# RK3566_DDR4.net
KiCad netlist of a schematic drawn in Altium Designer
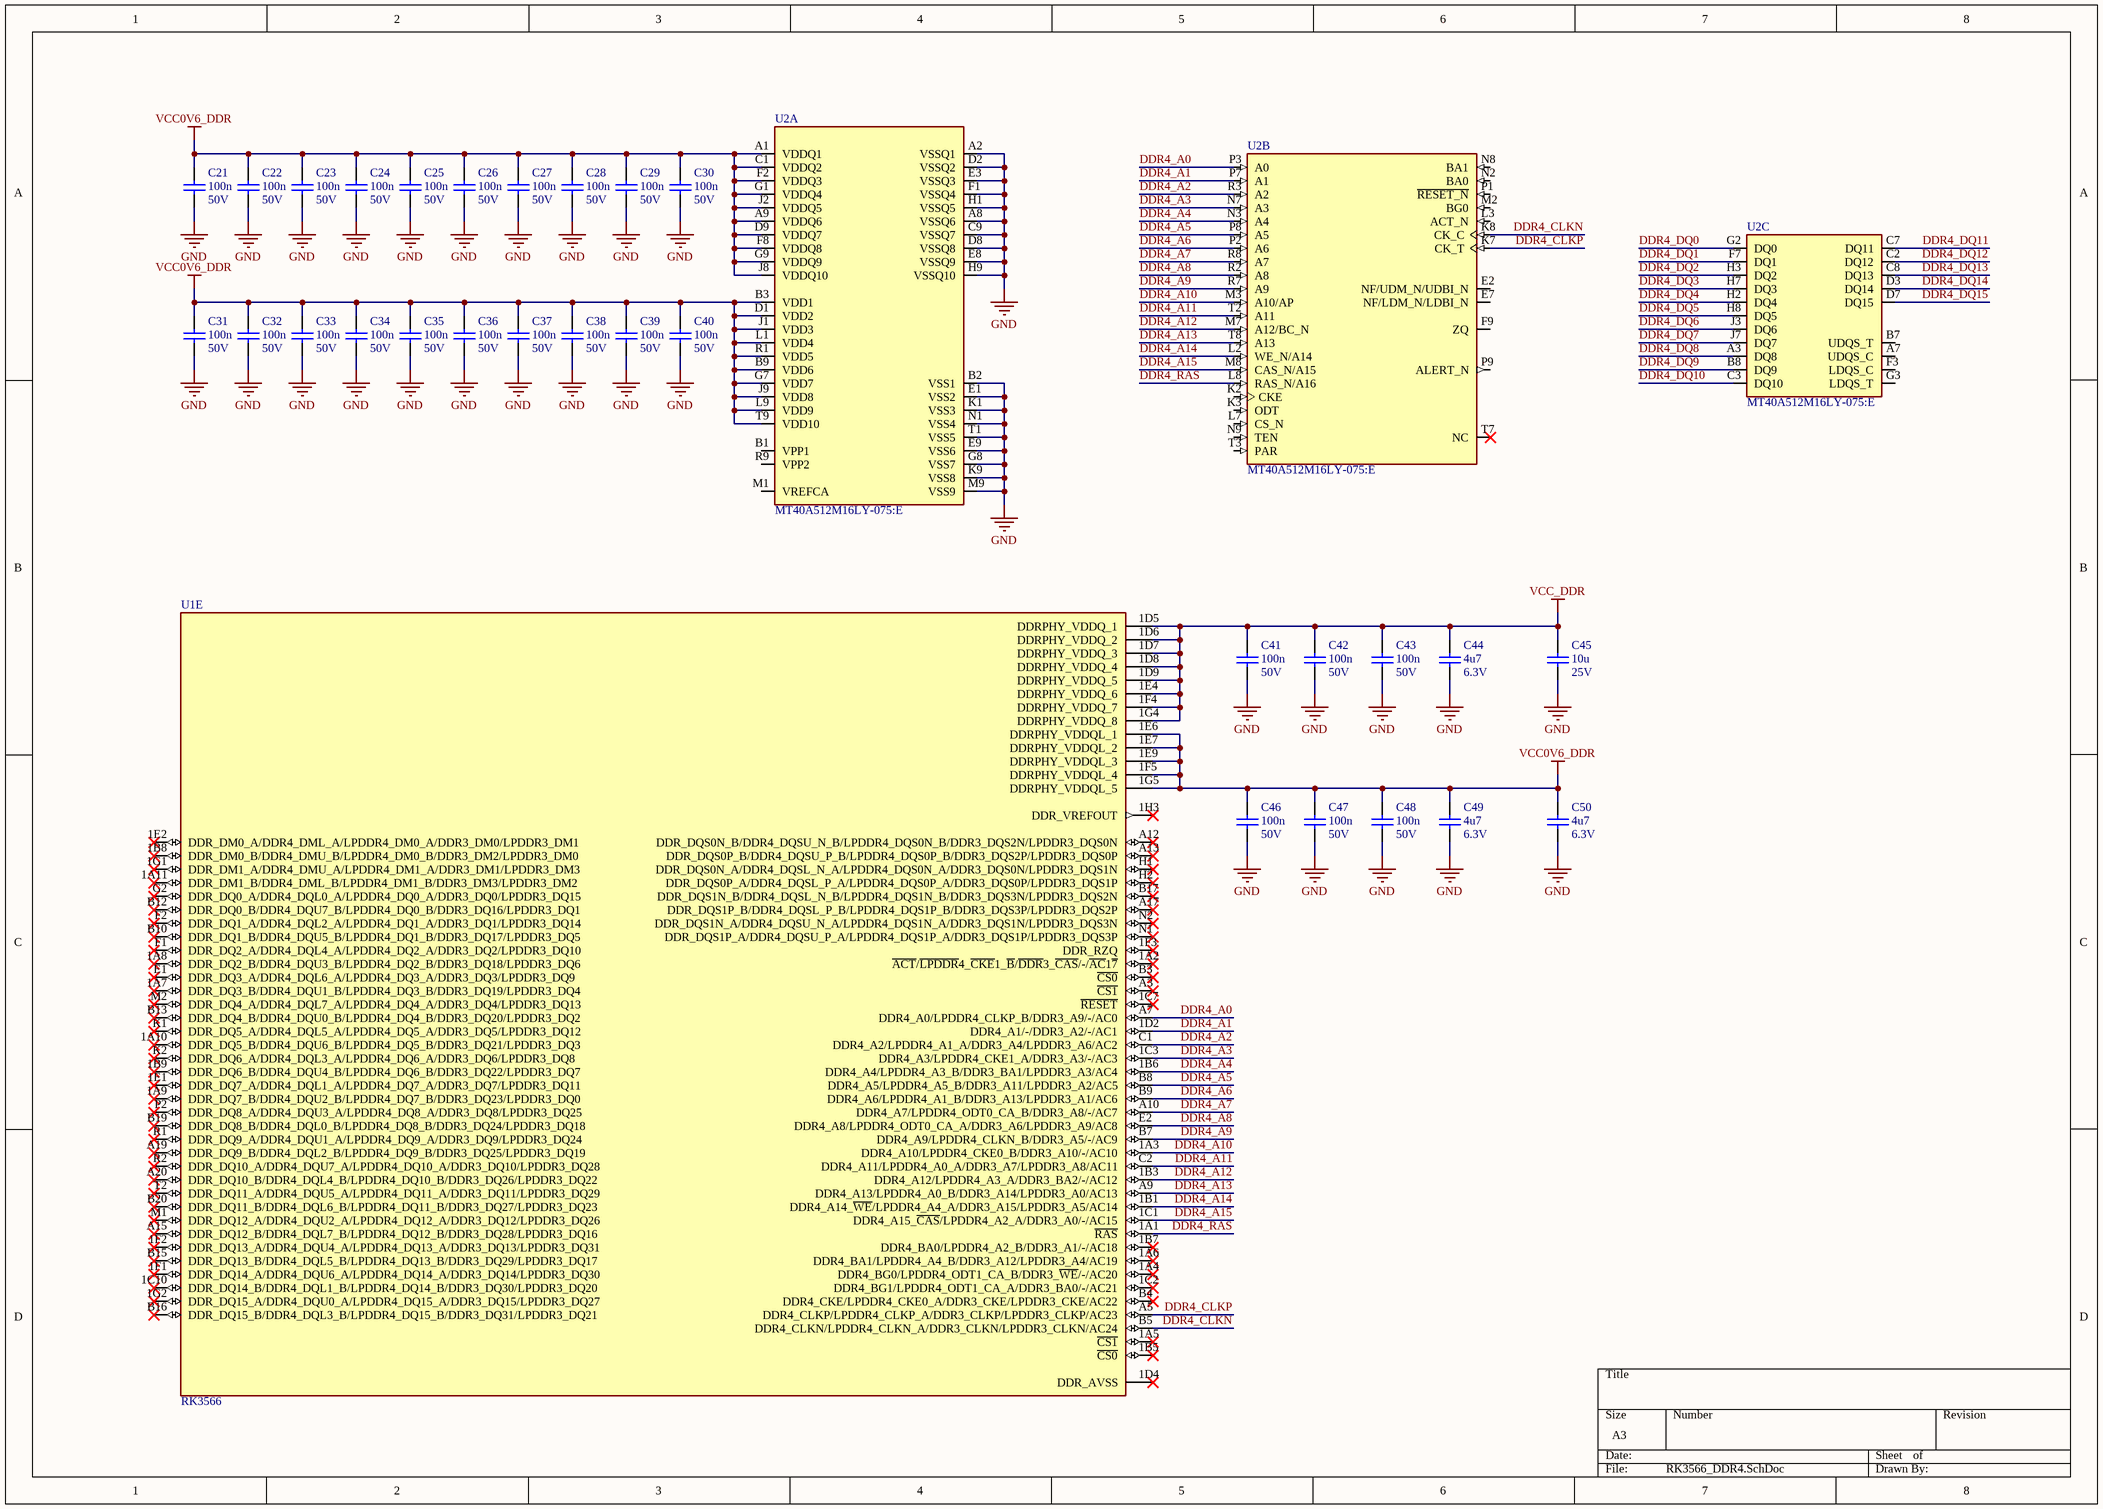
[diagram p0: RK3566_DDR4.SchDoc]

(export (version "E")
  (design (tool "Eeschema 10.0.6"))
  (components
    (comp (ref "C21")
      (value "100n")
      (description "CAP 100N 50V X7R 0402")
      (fields (field (name "VOLTAGE") "50V") (field (name "Comment") "GRM155R71H104KE14D"))
      (libsource (lib "PersonalAltiumLibrary") (part "GRM155R71H104KE14D"))
    )
    (comp (ref "C22")
      (value "100n")
      (description "CAP 100N 50V X7R 0402")
      (fields (field (name "VOLTAGE") "50V") (field (name "Comment") "GRM155R71H104KE14D"))
      (libsource (lib "PersonalAltiumLibrary") (part "GRM155R71H104KE14D"))
    )
    (comp (ref "C23")
      (value "100n")
      (description "CAP 100N 50V X7R 0402")
      (fields (field (name "VOLTAGE") "50V") (field (name "Comment") "GRM155R71H104KE14D"))
      (libsource (lib "PersonalAltiumLibrary") (part "GRM155R71H104KE14D"))
    )
    (comp (ref "C24")
      (value "100n")
      (description "CAP 100N 50V X7R 0402")
      (fields (field (name "VOLTAGE") "50V") (field (name "Comment") "GRM155R71H104KE14D"))
      (libsource (lib "PersonalAltiumLibrary") (part "GRM155R71H104KE14D"))
    )
    (comp (ref "C25")
      (value "100n")
      (description "CAP 100N 50V X7R 0402")
      (fields (field (name "VOLTAGE") "50V") (field (name "Comment") "GRM155R71H104KE14D"))
      (libsource (lib "PersonalAltiumLibrary") (part "GRM155R71H104KE14D"))
    )
    (comp (ref "C26")
      (value "100n")
      (description "CAP 100N 50V X7R 0402")
      (fields (field (name "VOLTAGE") "50V") (field (name "Comment") "GRM155R71H104KE14D"))
      (libsource (lib "PersonalAltiumLibrary") (part "GRM155R71H104KE14D"))
    )
    (comp (ref "C27")
      (value "100n")
      (description "CAP 100N 50V X7R 0402")
      (fields (field (name "VOLTAGE") "50V") (field (name "Comment") "GRM155R71H104KE14D"))
      (libsource (lib "PersonalAltiumLibrary") (part "GRM155R71H104KE14D"))
    )
    (comp (ref "C28")
      (value "100n")
      (description "CAP 100N 50V X7R 0402")
      (fields (field (name "VOLTAGE") "50V") (field (name "Comment") "GRM155R71H104KE14D"))
      (libsource (lib "PersonalAltiumLibrary") (part "GRM155R71H104KE14D"))
    )
    (comp (ref "C29")
      (value "100n")
      (description "CAP 100N 50V X7R 0402")
      (fields (field (name "VOLTAGE") "50V") (field (name "Comment") "GRM155R71H104KE14D"))
      (libsource (lib "PersonalAltiumLibrary") (part "GRM155R71H104KE14D"))
    )
    (comp (ref "C30")
      (value "100n")
      (description "CAP 100N 50V X7R 0402")
      (fields (field (name "VOLTAGE") "50V") (field (name "Comment") "GRM155R71H104KE14D"))
      (libsource (lib "PersonalAltiumLibrary") (part "GRM155R71H104KE14D"))
    )
    (comp (ref "C31")
      (value "100n")
      (description "CAP 100N 50V X7R 0402")
      (fields (field (name "VOLTAGE") "50V") (field (name "Comment") "GRM155R71H104KE14D"))
      (libsource (lib "PersonalAltiumLibrary") (part "GRM155R71H104KE14D"))
    )
    (comp (ref "C32")
      (value "100n")
      (description "CAP 100N 50V X7R 0402")
      (fields (field (name "VOLTAGE") "50V") (field (name "Comment") "GRM155R71H104KE14D"))
      (libsource (lib "PersonalAltiumLibrary") (part "GRM155R71H104KE14D"))
    )
    (comp (ref "C33")
      (value "100n")
      (description "CAP 100N 50V X7R 0402")
      (fields (field (name "VOLTAGE") "50V") (field (name "Comment") "GRM155R71H104KE14D"))
      (libsource (lib "PersonalAltiumLibrary") (part "GRM155R71H104KE14D"))
    )
    (comp (ref "C34")
      (value "100n")
      (description "CAP 100N 50V X7R 0402")
      (fields (field (name "VOLTAGE") "50V") (field (name "Comment") "GRM155R71H104KE14D"))
      (libsource (lib "PersonalAltiumLibrary") (part "GRM155R71H104KE14D"))
    )
    (comp (ref "C35")
      (value "100n")
      (description "CAP 100N 50V X7R 0402")
      (fields (field (name "VOLTAGE") "50V") (field (name "Comment") "GRM155R71H104KE14D"))
      (libsource (lib "PersonalAltiumLibrary") (part "GRM155R71H104KE14D"))
    )
    (comp (ref "C36")
      (value "100n")
      (description "CAP 100N 50V X7R 0402")
      (fields (field (name "VOLTAGE") "50V") (field (name "Comment") "GRM155R71H104KE14D"))
      (libsource (lib "PersonalAltiumLibrary") (part "GRM155R71H104KE14D"))
    )
    (comp (ref "C37")
      (value "100n")
      (description "CAP 100N 50V X7R 0402")
      (fields (field (name "VOLTAGE") "50V") (field (name "Comment") "GRM155R71H104KE14D"))
      (libsource (lib "PersonalAltiumLibrary") (part "GRM155R71H104KE14D"))
    )
    (comp (ref "C38")
      (value "100n")
      (description "CAP 100N 50V X7R 0402")
      (fields (field (name "VOLTAGE") "50V") (field (name "Comment") "GRM155R71H104KE14D"))
      (libsource (lib "PersonalAltiumLibrary") (part "GRM155R71H104KE14D"))
    )
    (comp (ref "C39")
      (value "100n")
      (description "CAP 100N 50V X7R 0402")
      (fields (field (name "VOLTAGE") "50V") (field (name "Comment") "GRM155R71H104KE14D"))
      (libsource (lib "PersonalAltiumLibrary") (part "GRM155R71H104KE14D"))
    )
    (comp (ref "C40")
      (value "100n")
      (description "CAP 100N 50V X7R 0402")
      (fields (field (name "VOLTAGE") "50V") (field (name "Comment") "GRM155R71H104KE14D"))
      (libsource (lib "PersonalAltiumLibrary") (part "GRM155R71H104KE14D"))
    )
    (comp (ref "C41")
      (value "100n")
      (description "CAP 100N 50V X7R 0402")
      (fields (field (name "VOLTAGE") "50V") (field (name "Comment") "GRM155R71H104KE14D"))
      (libsource (lib "PersonalAltiumLibrary") (part "GRM155R71H104KE14D"))
    )
    (comp (ref "C42")
      (value "100n")
      (description "CAP 100N 50V X7R 0402")
      (fields (field (name "VOLTAGE") "50V") (field (name "Comment") "GRM155R71H104KE14D"))
      (libsource (lib "PersonalAltiumLibrary") (part "GRM155R71H104KE14D"))
    )
    (comp (ref "C43")
      (value "100n")
      (description "CAP 100N 50V X7R 0402")
      (fields (field (name "VOLTAGE") "50V") (field (name "Comment") "GRM155R71H104KE14D"))
      (libsource (lib "PersonalAltiumLibrary") (part "GRM155R71H104KE14D"))
    )
    (comp (ref "C44")
      (value "4u7")
      (description "CAP 4.7U 6.3V X5R 0402")
      (fields (field (name "VOLTAGE") "6.3V") (field (name "Comment") "GRM155R60J475ME47D"))
      (libsource (lib "PersonalAltiumLibrary") (part "GRM155R60J475ME47D"))
    )
    (comp (ref "C45")
      (value "10u")
      (description "CAP 10U 25V X5R 0603")
      (fields (field (name "VOLTAGE") "25V") (field (name "Comment") "GRM188R61E106MA73D"))
      (libsource (lib "PersonalAltiumLibrary") (part "GRM188R61E106MA73D"))
    )
    (comp (ref "C46")
      (value "100n")
      (description "CAP 100N 50V X7R 0402")
      (fields (field (name "VOLTAGE") "50V") (field (name "Comment") "GRM155R71H104KE14D"))
      (libsource (lib "PersonalAltiumLibrary") (part "GRM155R71H104KE14D"))
    )
    (comp (ref "C47")
      (value "100n")
      (description "CAP 100N 50V X7R 0402")
      (fields (field (name "VOLTAGE") "50V") (field (name "Comment") "GRM155R71H104KE14D"))
      (libsource (lib "PersonalAltiumLibrary") (part "GRM155R71H104KE14D"))
    )
    (comp (ref "C48")
      (value "100n")
      (description "CAP 100N 50V X7R 0402")
      (fields (field (name "VOLTAGE") "50V") (field (name "Comment") "GRM155R71H104KE14D"))
      (libsource (lib "PersonalAltiumLibrary") (part "GRM155R71H104KE14D"))
    )
    (comp (ref "C49")
      (value "4u7")
      (description "CAP 4.7U 6.3V X5R 0402")
      (fields (field (name "VOLTAGE") "6.3V") (field (name "Comment") "GRM155R60J475ME47D"))
      (libsource (lib "PersonalAltiumLibrary") (part "GRM155R60J475ME47D"))
    )
    (comp (ref "C50")
      (value "4u7")
      (description "CAP 4.7U 6.3V X5R 0402")
      (fields (field (name "VOLTAGE") "6.3V") (field (name "Comment") "GRM155R60J475ME47D"))
      (libsource (lib "PersonalAltiumLibrary") (part "GRM155R60J475ME47D"))
    )
    (comp (ref "U1")
      (value "RK3566")
      (footprint "RK3566")
      (description "high-performance and low-power quad-core application processor")
      (fields (field (name "MF") "Fuzhou Rockchip Electronics Co"))
      (libsource (lib "PersonalAltiumLibrary") (part "RK3566"))
    )
    (comp (ref "U2")
      (value "MT40A512M16LY-075:E")
      (description "SDRAM - DDR4 Memory IC 8Gb (512M x 16) Parallel 1.33 GHz 96-FBGA (7.5x13.5)")
      (fields (field (name "MF") "Micron Technology Inc."))
      (libsource (lib "PersonalAltiumLibrary") (part "MT40A512M16LY-075{colon}E"))
    )
  )
  (nets
    (net (code "1") (name "/DDR4_A0") (class "Default")
      (node (ref "U1") (pin "A7") (pinfunction "DDR4_A0/LPDDR4_CLKP_B/DDR3_A9/-/AC0_A7") (pintype "bidirectional"))
      (node (ref "U2") (pin "P3") (pinfunction "A0_P3") (pintype "input"))
    )
    (net (code "2") (name "/DDR4_A1") (class "Default")
      (node (ref "U1") (pin "1D2") (pinfunction "DDR4_A1/-/DDR3_A2/-/AC1_1D2") (pintype "bidirectional"))
      (node (ref "U2") (pin "P7") (pinfunction "A1_P7") (pintype "input"))
    )
    (net (code "3") (name "/DDR4_A2") (class "Default")
      (node (ref "U1") (pin "C1") (pinfunction "DDR4_A2/LPDDR4_A1_A/DDR3_A4/LPDDR3_A6/AC2_C1") (pintype "bidirectional"))
      (node (ref "U2") (pin "R3") (pinfunction "A2_R3") (pintype "input"))
    )
    (net (code "4") (name "/DDR4_A3") (class "Default")
      (node (ref "U1") (pin "1C3") (pinfunction "DDR4_A3/LPDDR4_CKE1_A/DDR3_A3/-/AC3_1C3") (pintype "bidirectional"))
      (node (ref "U2") (pin "N7") (pinfunction "A3_N7") (pintype "input"))
    )
    (net (code "5") (name "/DDR4_A4") (class "Default")
      (node (ref "U1") (pin "1B6") (pinfunction "DDR4_A4/LPDDR4_A3_B/DDR3_BA1/LPDDR3_A3/AC4_1B6") (pintype "bidirectional"))
      (node (ref "U2") (pin "N3") (pinfunction "A4_N3") (pintype "input"))
    )
    (net (code "6") (name "/DDR4_A5") (class "Default")
      (node (ref "U1") (pin "B8") (pinfunction "DDR4_A5/LPDDR4_A5_B/DDR3_A11/LPDDR3_A2/AC5_B8") (pintype "bidirectional"))
      (node (ref "U2") (pin "P8") (pinfunction "A5_P8") (pintype "input"))
    )
    (net (code "7") (name "/DDR4_A6") (class "Default")
      (node (ref "U1") (pin "B9") (pinfunction "DDR4_A6/LPDDR4_A1_B/DDR3_A13/LPDDR3_A1/AC6_B9") (pintype "bidirectional"))
      (node (ref "U2") (pin "P2") (pinfunction "A6_P2") (pintype "input"))
    )
    (net (code "8") (name "/DDR4_A7") (class "Default")
      (node (ref "U1") (pin "A10") (pinfunction "DDR4_A7/LPDDR4_ODT0_CA_B/DDR3_A8/-/AC7_A10") (pintype "bidirectional"))
      (node (ref "U2") (pin "R8") (pinfunction "A7_R8") (pintype "input"))
    )
    (net (code "9") (name "/DDR4_A8") (class "Default")
      (node (ref "U1") (pin "E2") (pinfunction "DDR4_A8/LPDDR4_ODT0_CA_A/DDR3_A6/LPDDR3_A9/AC8_E2") (pintype "bidirectional"))
      (node (ref "U2") (pin "R2") (pinfunction "A8_R2") (pintype "input"))
    )
    (net (code "10") (name "/DDR4_A9") (class "Default")
      (node (ref "U1") (pin "B7") (pinfunction "DDR4_A9/LPDDR4_CLKN_B/DDR3_A5/-/AC9_B7") (pintype "bidirectional"))
      (node (ref "U2") (pin "R7") (pinfunction "A9_R7") (pintype "input"))
    )
    (net (code "11") (name "/DDR4_A10") (class "Default")
      (node (ref "U1") (pin "1A3") (pinfunction "DDR4_A10/LPDDR4_CKE0_B/DDR3_A10/-/AC10_1A3") (pintype "bidirectional"))
      (node (ref "U2") (pin "M3") (pinfunction "A10/AP_M3") (pintype "input"))
    )
    (net (code "12") (name "/DDR4_A11") (class "Default")
      (node (ref "U1") (pin "C2") (pinfunction "DDR4_A11/LPDDR4_A0_A/DDR3_A7/LPDDR3_A8/AC11_C2") (pintype "bidirectional"))
      (node (ref "U2") (pin "T2") (pinfunction "A11_T2") (pintype "input"))
    )
    (net (code "13") (name "/DDR4_A12") (class "Default")
      (node (ref "U1") (pin "1B3") (pinfunction "DDR4_A12/LPDDR4_A3_A/DDR3_BA2/-/AC12_1B3") (pintype "bidirectional"))
      (node (ref "U2") (pin "M7") (pinfunction "A12/BC_N_M7") (pintype "input"))
    )
    (net (code "14") (name "/DDR4_A13") (class "Default")
      (node (ref "U1") (pin "A9") (pinfunction "DDR4_A13/LPDDR4_A0_B/DDR3_A14/LPDDR3_A0/AC13_A9") (pintype "bidirectional"))
      (node (ref "U2") (pin "T8") (pinfunction "A13_T8") (pintype "input"))
    )
    (net (code "15") (name "/DDR4_A14") (class "Default")
      (node (ref "U1") (pin "1B1") (pinfunction "DDR4_A14_~{WE}/LPDDR4_A4_A/DDR3_A15/LPDDR3_A5/AC14_1B1") (pintype "bidirectional"))
      (node (ref "U2") (pin "L2") (pinfunction "WE_N/A14_L2") (pintype "input"))
    )
    (net (code "16") (name "/DDR4_A15") (class "Default")
      (node (ref "U1") (pin "1C1") (pinfunction "DDR4_A15_~{CAS}/LPDDR4_A2_A/DDR3_A0/-/AC15_1C1") (pintype "bidirectional"))
      (node (ref "U2") (pin "M8") (pinfunction "CAS_N/A15_M8") (pintype "input"))
    )
    (net (code "17") (name "/DDR4_CLKN") (class "Default")
      (node (ref "U1") (pin "B5") (pinfunction "DDR4_CLKN/LPDDR4_CLKN_A/DDR3_CLKN/LPDDR3_CLKN/AC24_B5") (pintype "bidirectional"))
      (node (ref "U2") (pin "K8") (pinfunction "CK_C_K8") (pintype "input"))
    )
    (net (code "18") (name "/DDR4_CLKP") (class "Default")
      (node (ref "U1") (pin "A5") (pinfunction "DDR4_CLKP/LPDDR4_CLKP_A/DDR3_CLKP/LPDDR3_CLKP/AC23_A5") (pintype "bidirectional"))
      (node (ref "U2") (pin "K7") (pinfunction "CK_T_K7") (pintype "input"))
    )
    (net (code "19") (name "/DDR4_DQ0") (class "Default")
      (node (ref "U2") (pin "G2") (pinfunction "DQ0_G2") (pintype "bidirectional"))
    )
    (net (code "20") (name "/DDR4_DQ1") (class "Default")
      (node (ref "U2") (pin "F7") (pinfunction "DQ1_F7") (pintype "bidirectional"))
    )
    (net (code "21") (name "/DDR4_DQ2") (class "Default")
      (node (ref "U2") (pin "H3") (pinfunction "DQ2_H3") (pintype "bidirectional"))
    )
    (net (code "22") (name "/DDR4_DQ3") (class "Default")
      (node (ref "U2") (pin "H7") (pinfunction "DQ3_H7") (pintype "bidirectional"))
    )
    (net (code "23") (name "/DDR4_DQ4") (class "Default")
      (node (ref "U2") (pin "H2") (pinfunction "DQ4_H2") (pintype "bidirectional"))
    )
    (net (code "24") (name "/DDR4_DQ5") (class "Default")
      (node (ref "U2") (pin "H8") (pinfunction "DQ5_H8") (pintype "bidirectional"))
    )
    (net (code "25") (name "/DDR4_DQ6") (class "Default")
      (node (ref "U2") (pin "J3") (pinfunction "DQ6_J3") (pintype "bidirectional"))
    )
    (net (code "26") (name "/DDR4_DQ7") (class "Default")
      (node (ref "U2") (pin "J7") (pinfunction "DQ7_J7") (pintype "bidirectional"))
    )
    (net (code "27") (name "/DDR4_DQ8") (class "Default")
      (node (ref "U2") (pin "A3") (pinfunction "DQ8_A3") (pintype "bidirectional"))
    )
    (net (code "28") (name "/DDR4_DQ9") (class "Default")
      (node (ref "U2") (pin "B8") (pinfunction "DQ9_B8") (pintype "bidirectional"))
    )
    (net (code "29") (name "/DDR4_DQ10") (class "Default")
      (node (ref "U2") (pin "C3") (pinfunction "DQ10_C3") (pintype "bidirectional"))
    )
    (net (code "30") (name "/DDR4_DQ11") (class "Default")
      (node (ref "U2") (pin "C7") (pinfunction "DQ11_C7") (pintype "bidirectional"))
    )
    (net (code "31") (name "/DDR4_DQ12") (class "Default")
      (node (ref "U2") (pin "C2") (pinfunction "DQ12_C2") (pintype "bidirectional"))
    )
    (net (code "32") (name "/DDR4_DQ13") (class "Default")
      (node (ref "U2") (pin "C8") (pinfunction "DQ13_C8") (pintype "bidirectional"))
    )
    (net (code "33") (name "/DDR4_DQ14") (class "Default")
      (node (ref "U2") (pin "D3") (pinfunction "DQ14_D3") (pintype "bidirectional"))
    )
    (net (code "34") (name "/DDR4_DQ15") (class "Default")
      (node (ref "U2") (pin "D7") (pinfunction "DQ15_D7") (pintype "bidirectional"))
    )
    (net (code "35") (name "/DDR4_RAS") (class "Default")
      (node (ref "U1") (pin "1A1") (pinfunction "~{RAS}_1A1") (pintype "bidirectional"))
      (node (ref "U2") (pin "L8") (pinfunction "RAS_N/A16_L8") (pintype "input"))
    )
    (net (code "36") (name "GND") (class "Default")
      (node (ref "C21") (pin "2") (pinfunction "2_2") (pintype "passive"))
      (node (ref "C22") (pin "2") (pinfunction "2_2") (pintype "passive"))
      (node (ref "C23") (pin "2") (pinfunction "2_2") (pintype "passive"))
      (node (ref "C24") (pin "2") (pinfunction "2_2") (pintype "passive"))
      (node (ref "C25") (pin "2") (pinfunction "2_2") (pintype "passive"))
      (node (ref "C26") (pin "2") (pinfunction "2_2") (pintype "passive"))
      (node (ref "C27") (pin "2") (pinfunction "2_2") (pintype "passive"))
      (node (ref "C28") (pin "2") (pinfunction "2_2") (pintype "passive"))
      (node (ref "C29") (pin "2") (pinfunction "2_2") (pintype "passive"))
      (node (ref "C30") (pin "2") (pinfunction "2_2") (pintype "passive"))
      (node (ref "C31") (pin "2") (pinfunction "2_2") (pintype "passive"))
      (node (ref "C32") (pin "2") (pinfunction "2_2") (pintype "passive"))
      (node (ref "C33") (pin "2") (pinfunction "2_2") (pintype "passive"))
      (node (ref "C34") (pin "2") (pinfunction "2_2") (pintype "passive"))
      (node (ref "C35") (pin "2") (pinfunction "2_2") (pintype "passive"))
      (node (ref "C36") (pin "2") (pinfunction "2_2") (pintype "passive"))
      (node (ref "C37") (pin "2") (pinfunction "2_2") (pintype "passive"))
      (node (ref "C38") (pin "2") (pinfunction "2_2") (pintype "passive"))
      (node (ref "C39") (pin "2") (pinfunction "2_2") (pintype "passive"))
      (node (ref "C40") (pin "2") (pinfunction "2_2") (pintype "passive"))
      (node (ref "C41") (pin "2") (pinfunction "2_2") (pintype "passive"))
      (node (ref "C42") (pin "2") (pinfunction "2_2") (pintype "passive"))
      (node (ref "C43") (pin "2") (pinfunction "2_2") (pintype "passive"))
      (node (ref "C44") (pin "2") (pinfunction "2_2") (pintype "passive"))
      (node (ref "C45") (pin "2") (pinfunction "2_2") (pintype "passive"))
      (node (ref "C46") (pin "2") (pinfunction "2_2") (pintype "passive"))
      (node (ref "C47") (pin "2") (pinfunction "2_2") (pintype "passive"))
      (node (ref "C48") (pin "2") (pinfunction "2_2") (pintype "passive"))
      (node (ref "C49") (pin "2") (pinfunction "2_2") (pintype "passive"))
      (node (ref "C50") (pin "2") (pinfunction "2_2") (pintype "passive"))
      (node (ref "U2") (pin "A2") (pinfunction "VSSQ1_A2") (pintype "power_in"))
      (node (ref "U2") (pin "A8") (pinfunction "VSSQ6_A8") (pintype "power_in"))
      (node (ref "U2") (pin "B2") (pinfunction "VSS1_B2") (pintype "power_in"))
      (node (ref "U2") (pin "C9") (pinfunction "VSSQ7_C9") (pintype "power_in"))
      (node (ref "U2") (pin "D2") (pinfunction "VSSQ2_D2") (pintype "power_in"))
      (node (ref "U2") (pin "D8") (pinfunction "VSSQ8_D8") (pintype "power_in"))
      (node (ref "U2") (pin "E1") (pinfunction "VSS2_E1") (pintype "power_in"))
      (node (ref "U2") (pin "E3") (pinfunction "VSSQ3_E3") (pintype "power_in"))
      (node (ref "U2") (pin "E8") (pinfunction "VSSQ9_E8") (pintype "power_in"))
      (node (ref "U2") (pin "E9") (pinfunction "VSS6_E9") (pintype "power_in"))
      (node (ref "U2") (pin "F1") (pinfunction "VSSQ4_F1") (pintype "power_in"))
      (node (ref "U2") (pin "G8") (pinfunction "VSS7_G8") (pintype "power_in"))
      (node (ref "U2") (pin "H1") (pinfunction "VSSQ5_H1") (pintype "power_in"))
      (node (ref "U2") (pin "H9") (pinfunction "VSSQ10_H9") (pintype "power_in"))
      (node (ref "U2") (pin "K1") (pinfunction "VSS3_K1") (pintype "power_in"))
      (node (ref "U2") (pin "K9") (pinfunction "VSS8_K9") (pintype "power_in"))
      (node (ref "U2") (pin "M9") (pinfunction "VSS9_M9") (pintype "power_in"))
      (node (ref "U2") (pin "N1") (pinfunction "VSS4_N1") (pintype "power_in"))
      (node (ref "U2") (pin "T1") (pinfunction "VSS5_T1") (pintype "power_in"))
    )
    (net (code "37") (name "VCC0V6_DDR") (class "Default")
      (node (ref "C21") (pin "1") (pinfunction "1_1") (pintype "passive"))
      (node (ref "C22") (pin "1") (pinfunction "1_1") (pintype "passive"))
      (node (ref "C23") (pin "1") (pinfunction "1_1") (pintype "passive"))
      (node (ref "C24") (pin "1") (pinfunction "1_1") (pintype "passive"))
      (node (ref "C25") (pin "1") (pinfunction "1_1") (pintype "passive"))
      (node (ref "C26") (pin "1") (pinfunction "1_1") (pintype "passive"))
      (node (ref "C27") (pin "1") (pinfunction "1_1") (pintype "passive"))
      (node (ref "C28") (pin "1") (pinfunction "1_1") (pintype "passive"))
      (node (ref "C29") (pin "1") (pinfunction "1_1") (pintype "passive"))
      (node (ref "C30") (pin "1") (pinfunction "1_1") (pintype "passive"))
      (node (ref "C31") (pin "1") (pinfunction "1_1") (pintype "passive"))
      (node (ref "C32") (pin "1") (pinfunction "1_1") (pintype "passive"))
      (node (ref "C33") (pin "1") (pinfunction "1_1") (pintype "passive"))
      (node (ref "C34") (pin "1") (pinfunction "1_1") (pintype "passive"))
      (node (ref "C35") (pin "1") (pinfunction "1_1") (pintype "passive"))
      (node (ref "C36") (pin "1") (pinfunction "1_1") (pintype "passive"))
      (node (ref "C37") (pin "1") (pinfunction "1_1") (pintype "passive"))
      (node (ref "C38") (pin "1") (pinfunction "1_1") (pintype "passive"))
      (node (ref "C39") (pin "1") (pinfunction "1_1") (pintype "passive"))
      (node (ref "C40") (pin "1") (pinfunction "1_1") (pintype "passive"))
      (node (ref "C46") (pin "1") (pinfunction "1_1") (pintype "passive"))
      (node (ref "C47") (pin "1") (pinfunction "1_1") (pintype "passive"))
      (node (ref "C48") (pin "1") (pinfunction "1_1") (pintype "passive"))
      (node (ref "C49") (pin "1") (pinfunction "1_1") (pintype "passive"))
      (node (ref "C50") (pin "1") (pinfunction "1_1") (pintype "passive"))
      (node (ref "U1") (pin "1E6") (pinfunction "DDRPHY_VDDQL_1_1E6") (pintype "power_in"))
      (node (ref "U1") (pin "1E7") (pinfunction "DDRPHY_VDDQL_2_1E7") (pintype "power_in"))
      (node (ref "U1") (pin "1E9") (pinfunction "DDRPHY_VDDQL_3_1E9") (pintype "power_in"))
      (node (ref "U1") (pin "1F5") (pinfunction "DDRPHY_VDDQL_4_1F5") (pintype "power_in"))
      (node (ref "U1") (pin "1G5") (pinfunction "DDRPHY_VDDQL_5_1G5") (pintype "power_in"))
      (node (ref "U2") (pin "A1") (pinfunction "VDDQ1_A1") (pintype "power_in"))
      (node (ref "U2") (pin "A9") (pinfunction "VDDQ6_A9") (pintype "power_in"))
      (node (ref "U2") (pin "B3") (pinfunction "VDD1_B3") (pintype "power_in"))
      (node (ref "U2") (pin "B9") (pinfunction "VDD6_B9") (pintype "power_in"))
      (node (ref "U2") (pin "C1") (pinfunction "VDDQ2_C1") (pintype "power_in"))
      (node (ref "U2") (pin "D1") (pinfunction "VDD2_D1") (pintype "power_in"))
      (node (ref "U2") (pin "D9") (pinfunction "VDDQ7_D9") (pintype "power_in"))
      (node (ref "U2") (pin "F2") (pinfunction "VDDQ3_F2") (pintype "power_in"))
      (node (ref "U2") (pin "F8") (pinfunction "VDDQ8_F8") (pintype "power_in"))
      (node (ref "U2") (pin "G1") (pinfunction "VDDQ4_G1") (pintype "power_in"))
      (node (ref "U2") (pin "G7") (pinfunction "VDD7_G7") (pintype "power_in"))
      (node (ref "U2") (pin "G9") (pinfunction "VDDQ9_G9") (pintype "power_in"))
      (node (ref "U2") (pin "J1") (pinfunction "VDD3_J1") (pintype "power_in"))
      (node (ref "U2") (pin "J2") (pinfunction "VDDQ5_J2") (pintype "power_in"))
      (node (ref "U2") (pin "J8") (pinfunction "VDDQ10_J8") (pintype "power_in"))
      (node (ref "U2") (pin "J9") (pinfunction "VDD8_J9") (pintype "power_in"))
      (node (ref "U2") (pin "L1") (pinfunction "VDD4_L1") (pintype "power_in"))
      (node (ref "U2") (pin "L9") (pinfunction "VDD9_L9") (pintype "power_in"))
      (node (ref "U2") (pin "R1") (pinfunction "VDD5_R1") (pintype "power_in"))
      (node (ref "U2") (pin "T9") (pinfunction "VDD10_T9") (pintype "power_in"))
    )
    (net (code "38") (name "VCC_DDR") (class "Default")
      (node (ref "C41") (pin "1") (pinfunction "1_1") (pintype "passive"))
      (node (ref "C42") (pin "1") (pinfunction "1_1") (pintype "passive"))
      (node (ref "C43") (pin "1") (pinfunction "1_1") (pintype "passive"))
      (node (ref "C44") (pin "1") (pinfunction "1_1") (pintype "passive"))
      (node (ref "C45") (pin "1") (pinfunction "1_1") (pintype "passive"))
      (node (ref "U1") (pin "1D5") (pinfunction "DDRPHY_VDDQ_1_1D5") (pintype "power_in"))
      (node (ref "U1") (pin "1D6") (pinfunction "DDRPHY_VDDQ_2_1D6") (pintype "power_in"))
      (node (ref "U1") (pin "1D7") (pinfunction "DDRPHY_VDDQ_3_1D7") (pintype "power_in"))
      (node (ref "U1") (pin "1D8") (pinfunction "DDRPHY_VDDQ_4_1D8") (pintype "power_in"))
      (node (ref "U1") (pin "1D9") (pinfunction "DDRPHY_VDDQ_5_1D9") (pintype "power_in"))
      (node (ref "U1") (pin "1E4") (pinfunction "DDRPHY_VDDQ_6_1E4") (pintype "power_in"))
      (node (ref "U1") (pin "1F4") (pinfunction "DDRPHY_VDDQ_7_1F4") (pintype "power_in"))
      (node (ref "U1") (pin "1G4") (pinfunction "DDRPHY_VDDQ_8_1G4") (pintype "power_in"))
    )
    (net (code "39") (name "unconnected-(U1E-DDR4_BA0{slash}LPDDR4_A2_B{slash}DDR3_A1{slash}-{slash}AC18-Pad1B7)") (class "Default")
      (node (ref "U1") (pin "1B7") (pinfunction "DDR4_BA0/LPDDR4_A2_B/DDR3_A1/-/AC18_1B7") (pintype "bidirectional+no_connect"))
    )
    (net (code "40") (name "unconnected-(U1E-DDR4_BA1{slash}LPDDR4_A4_B{slash}DDR3_A12{slash}LPDDR3_A4{slash}AC19-Pad1A6)") (class "Default")
      (node (ref "U1") (pin "1A6") (pinfunction "DDR4_BA1/LPDDR4_A4_B/DDR3_A12/LPDDR3_A4/AC19_1A6") (pintype "bidirectional+no_connect"))
    )
    (net (code "41") (name "unconnected-(U1E-DDR4_BG0{slash}LPDDR4_ODT1_CA_B{slash}DDR3_~{WE}{slash}-{slash}AC20-Pad1A4)") (class "Default")
      (node (ref "U1") (pin "1A4") (pinfunction "DDR4_BG0/LPDDR4_ODT1_CA_B/DDR3_~{WE}/-/AC20_1A4") (pintype "bidirectional+no_connect"))
    )
    (net (code "42") (name "unconnected-(U1E-DDR4_BG1{slash}LPDDR4_ODT1_CA_A{slash}DDR3_BA0{slash}-{slash}AC21-Pad1C2)") (class "Default")
      (node (ref "U1") (pin "1C2") (pinfunction "DDR4_BG1/LPDDR4_ODT1_CA_A/DDR3_BA0/-/AC21_1C2") (pintype "bidirectional+no_connect"))
    )
    (net (code "43") (name "unconnected-(U1E-DDR4_CKE{slash}LPDDR4_CKE0_A{slash}DDR3_CKE{slash}LPDDR3_CKE{slash}AC22-PadB4)") (class "Default")
      (node (ref "U1") (pin "B4") (pinfunction "DDR4_CKE/LPDDR4_CKE0_A/DDR3_CKE/LPDDR3_CKE/AC22_B4") (pintype "bidirectional+no_connect"))
    )
    (net (code "44") (name "unconnected-(U1E-DDR_AVSS-Pad1D4)") (class "Default")
      (node (ref "U1") (pin "1D4") (pinfunction "DDR_AVSS_1D4") (pintype "power_in+no_connect"))
    )
    (net (code "45") (name "unconnected-(U1E-DDR_DM0_A{slash}DDR4_DML_A{slash}LPDDR4_DM0_A{slash}DDR3_DM0{slash}LPDDR3_DM1-Pad1E2)") (class "Default")
      (node (ref "U1") (pin "1E2") (pinfunction "DDR_DM0_A/DDR4_DML_A/LPDDR4_DM0_A/DDR3_DM0/LPDDR3_DM1_1E2") (pintype "bidirectional+no_connect"))
    )
    (net (code "46") (name "unconnected-(U1E-DDR_DM0_B{slash}DDR4_DMU_B{slash}LPDDR4_DM0_B{slash}DDR3_DM2{slash}LPDDR3_DM0-Pad1B8)") (class "Default")
      (node (ref "U1") (pin "1B8") (pinfunction "DDR_DM0_B/DDR4_DMU_B/LPDDR4_DM0_B/DDR3_DM2/LPDDR3_DM0_1B8") (pintype "bidirectional+no_connect"))
    )
    (net (code "47") (name "unconnected-(U1E-DDR_DM1_A{slash}DDR4_DMU_A{slash}LPDDR4_DM1_A{slash}DDR3_DM1{slash}LPDDR3_DM3-Pad1G1)") (class "Default")
      (node (ref "U1") (pin "1G1") (pinfunction "DDR_DM1_A/DDR4_DMU_A/LPDDR4_DM1_A/DDR3_DM1/LPDDR3_DM3_1G1") (pintype "bidirectional+no_connect"))
    )
    (net (code "48") (name "unconnected-(U1E-DDR_DM1_B{slash}DDR4_DML_B{slash}LPDDR4_DM1_B{slash}DDR3_DM3{slash}LPDDR3_DM2-Pad1A11)") (class "Default")
      (node (ref "U1") (pin "1A11") (pinfunction "DDR_DM1_B/DDR4_DML_B/LPDDR4_DM1_B/DDR3_DM3/LPDDR3_DM2_1A11") (pintype "bidirectional+no_connect"))
    )
    (net (code "49") (name "unconnected-(U1E-DDR_DQ0_A{slash}DDR4_DQL0_A{slash}LPDDR4_DQ0_A{slash}DDR3_DQ0{slash}LPDDR3_DQ15-PadG2)") (class "Default")
      (node (ref "U1") (pin "G2") (pinfunction "DDR_DQ0_A/DDR4_DQL0_A/LPDDR4_DQ0_A/DDR3_DQ0/LPDDR3_DQ15_G2") (pintype "bidirectional+no_connect"))
    )
    (net (code "50") (name "unconnected-(U1E-DDR_DQ0_B{slash}DDR4_DQU7_B{slash}LPDDR4_DQ0_B{slash}DDR3_DQ16{slash}LPDDR3_DQ1-PadB12)") (class "Default")
      (node (ref "U1") (pin "B12") (pinfunction "DDR_DQ0_B/DDR4_DQU7_B/LPDDR4_DQ0_B/DDR3_DQ16/LPDDR3_DQ1_B12") (pintype "bidirectional+no_connect"))
    )
    (net (code "51") (name "unconnected-(U1E-DDR_DQ1_A{slash}DDR4_DQL2_A{slash}LPDDR4_DQ1_A{slash}DDR3_DQ1{slash}LPDDR3_DQ14-PadF2)") (class "Default")
      (node (ref "U1") (pin "F2") (pinfunction "DDR_DQ1_A/DDR4_DQL2_A/LPDDR4_DQ1_A/DDR3_DQ1/LPDDR3_DQ14_F2") (pintype "bidirectional+no_connect"))
    )
    (net (code "52") (name "unconnected-(U1E-DDR_DQ1_B{slash}DDR4_DQU5_B{slash}LPDDR4_DQ1_B{slash}DDR3_DQ17{slash}LPDDR3_DQ5-PadB10)") (class "Default")
      (node (ref "U1") (pin "B10") (pinfunction "DDR_DQ1_B/DDR4_DQU5_B/LPDDR4_DQ1_B/DDR3_DQ17/LPDDR3_DQ5_B10") (pintype "bidirectional+no_connect"))
    )
    (net (code "53") (name "unconnected-(U1E-DDR_DQ2_A{slash}DDR4_DQL4_A{slash}LPDDR4_DQ2_A{slash}DDR3_DQ2{slash}LPDDR3_DQ10-PadF1)") (class "Default")
      (node (ref "U1") (pin "F1") (pinfunction "DDR_DQ2_A/DDR4_DQL4_A/LPDDR4_DQ2_A/DDR3_DQ2/LPDDR3_DQ10_F1") (pintype "bidirectional+no_connect"))
    )
    (net (code "54") (name "unconnected-(U1E-DDR_DQ2_B{slash}DDR4_DQU3_B{slash}LPDDR4_DQ2_B{slash}DDR3_DQ18{slash}LPDDR3_DQ6-Pad1A8)") (class "Default")
      (node (ref "U1") (pin "1A8") (pinfunction "DDR_DQ2_B/DDR4_DQU3_B/LPDDR4_DQ2_B/DDR3_DQ18/LPDDR3_DQ6_1A8") (pintype "bidirectional+no_connect"))
    )
    (net (code "55") (name "unconnected-(U1E-DDR_DQ3_A{slash}DDR4_DQL6_A{slash}LPDDR4_DQ3_A{slash}DDR3_DQ3{slash}LPDDR3_DQ9-PadE1)") (class "Default")
      (node (ref "U1") (pin "E1") (pinfunction "DDR_DQ3_A/DDR4_DQL6_A/LPDDR4_DQ3_A/DDR3_DQ3/LPDDR3_DQ9_E1") (pintype "bidirectional+no_connect"))
    )
    (net (code "56") (name "unconnected-(U1E-DDR_DQ3_B{slash}DDR4_DQU1_B{slash}LPDDR4_DQ3_B{slash}DDR3_DQ19{slash}LPDDR3_DQ4-Pad1A7)") (class "Default")
      (node (ref "U1") (pin "1A7") (pinfunction "DDR_DQ3_B/DDR4_DQU1_B/LPDDR4_DQ3_B/DDR3_DQ19/LPDDR3_DQ4_1A7") (pintype "bidirectional+no_connect"))
    )
    (net (code "57") (name "unconnected-(U1E-DDR_DQ4_A{slash}DDR4_DQL7_A{slash}LPDDR4_DQ4_A{slash}DDR3_DQ4{slash}LPDDR3_DQ13-PadM2)") (class "Default")
      (node (ref "U1") (pin "M2") (pinfunction "DDR_DQ4_A/DDR4_DQL7_A/LPDDR4_DQ4_A/DDR3_DQ4/LPDDR3_DQ13_M2") (pintype "bidirectional+no_connect"))
    )
    (net (code "58") (name "unconnected-(U1E-DDR_DQ4_B{slash}DDR4_DQU0_B{slash}LPDDR4_DQ4_B{slash}DDR3_DQ20{slash}LPDDR3_DQ2-PadB13)") (class "Default")
      (node (ref "U1") (pin "B13") (pinfunction "DDR_DQ4_B/DDR4_DQU0_B/LPDDR4_DQ4_B/DDR3_DQ20/LPDDR3_DQ2_B13") (pintype "bidirectional+no_connect"))
    )
    (net (code "59") (name "unconnected-(U1E-DDR_DQ5_A{slash}DDR4_DQL5_A{slash}LPDDR4_DQ5_A{slash}DDR3_DQ5{slash}LPDDR3_DQ12-PadK1)") (class "Default")
      (node (ref "U1") (pin "K1") (pinfunction "DDR_DQ5_A/DDR4_DQL5_A/LPDDR4_DQ5_A/DDR3_DQ5/LPDDR3_DQ12_K1") (pintype "bidirectional+no_connect"))
    )
    (net (code "60") (name "unconnected-(U1E-DDR_DQ5_B{slash}DDR4_DQU6_B{slash}LPDDR4_DQ5_B{slash}DDR3_DQ21{slash}LPDDR3_DQ3-Pad1A10)") (class "Default")
      (node (ref "U1") (pin "1A10") (pinfunction "DDR_DQ5_B/DDR4_DQU6_B/LPDDR4_DQ5_B/DDR3_DQ21/LPDDR3_DQ3_1A10") (pintype "bidirectional+no_connect"))
    )
    (net (code "61") (name "unconnected-(U1E-DDR_DQ6_A{slash}DDR4_DQL3_A{slash}LPDDR4_DQ6_A{slash}DDR3_DQ6{slash}LPDDR3_DQ8-PadK2)") (class "Default")
      (node (ref "U1") (pin "K2") (pinfunction "DDR_DQ6_A/DDR4_DQL3_A/LPDDR4_DQ6_A/DDR3_DQ6/LPDDR3_DQ8_K2") (pintype "bidirectional+no_connect"))
    )
    (net (code "62") (name "unconnected-(U1E-DDR_DQ6_B{slash}DDR4_DQU4_B{slash}LPDDR4_DQ6_B{slash}DDR3_DQ22{slash}LPDDR3_DQ7-Pad1B9)") (class "Default")
      (node (ref "U1") (pin "1B9") (pinfunction "DDR_DQ6_B/DDR4_DQU4_B/LPDDR4_DQ6_B/DDR3_DQ22/LPDDR3_DQ7_1B9") (pintype "bidirectional+no_connect"))
    )
    (net (code "63") (name "unconnected-(U1E-DDR_DQ7_A{slash}DDR4_DQL1_A{slash}LPDDR4_DQ7_A{slash}DDR3_DQ7{slash}LPDDR3_DQ11-Pad1E1)") (class "Default")
      (node (ref "U1") (pin "1E1") (pinfunction "DDR_DQ7_A/DDR4_DQL1_A/LPDDR4_DQ7_A/DDR3_DQ7/LPDDR3_DQ11_1E1") (pintype "bidirectional+no_connect"))
    )
    (net (code "64") (name "unconnected-(U1E-DDR_DQ7_B{slash}DDR4_DQU2_B{slash}LPDDR4_DQ7_B{slash}DDR3_DQ23{slash}LPDDR3_DQ0-Pad1A9)") (class "Default")
      (node (ref "U1") (pin "1A9") (pinfunction "DDR_DQ7_B/DDR4_DQU2_B/LPDDR4_DQ7_B/DDR3_DQ23/LPDDR3_DQ0_1A9") (pintype "bidirectional+no_connect"))
    )
    (net (code "65") (name "unconnected-(U1E-DDR_DQ8_A{slash}DDR4_DQU3_A{slash}LPDDR4_DQ8_A{slash}DDR3_DQ8{slash}LPDDR3_DQ25-PadP2)") (class "Default")
      (node (ref "U1") (pin "P2") (pinfunction "DDR_DQ8_A/DDR4_DQU3_A/LPDDR4_DQ8_A/DDR3_DQ8/LPDDR3_DQ25_P2") (pintype "bidirectional+no_connect"))
    )
    (net (code "66") (name "unconnected-(U1E-DDR_DQ8_B{slash}DDR4_DQL0_B{slash}LPDDR4_DQ8_B{slash}DDR3_DQ24{slash}LPDDR3_DQ18-PadB19)") (class "Default")
      (node (ref "U1") (pin "B19") (pinfunction "DDR_DQ8_B/DDR4_DQL0_B/LPDDR4_DQ8_B/DDR3_DQ24/LPDDR3_DQ18_B19") (pintype "bidirectional+no_connect"))
    )
    (net (code "67") (name "unconnected-(U1E-DDR_DQ9_A{slash}DDR4_DQU1_A{slash}LPDDR4_DQ9_A{slash}DDR3_DQ9{slash}LPDDR3_DQ24-PadR1)") (class "Default")
      (node (ref "U1") (pin "R1") (pinfunction "DDR_DQ9_A/DDR4_DQU1_A/LPDDR4_DQ9_A/DDR3_DQ9/LPDDR3_DQ24_R1") (pintype "bidirectional+no_connect"))
    )
    (net (code "68") (name "unconnected-(U1E-DDR_DQ9_B{slash}DDR4_DQL2_B{slash}LPDDR4_DQ9_B{slash}DDR3_DQ25{slash}LPDDR3_DQ19-PadA19)") (class "Default")
      (node (ref "U1") (pin "A19") (pinfunction "DDR_DQ9_B/DDR4_DQL2_B/LPDDR4_DQ9_B/DDR3_DQ25/LPDDR3_DQ19_A19") (pintype "bidirectional+no_connect"))
    )
    (net (code "69") (name "unconnected-(U1E-DDR_DQ10_A{slash}DDR4_DQU7_A{slash}LPDDR4_DQ10_A{slash}DDR3_DQ10{slash}LPDDR3_DQ28-PadR2)") (class "Default")
      (node (ref "U1") (pin "R2") (pinfunction "DDR_DQ10_A/DDR4_DQU7_A/LPDDR4_DQ10_A/DDR3_DQ10/LPDDR3_DQ28_R2") (pintype "bidirectional+no_connect"))
    )
    (net (code "70") (name "unconnected-(U1E-DDR_DQ10_B{slash}DDR4_DQL4_B{slash}LPDDR4_DQ10_B{slash}DDR3_DQ26{slash}LPDDR3_DQ22-PadA20)") (class "Default")
      (node (ref "U1") (pin "A20") (pinfunction "DDR_DQ10_B/DDR4_DQL4_B/LPDDR4_DQ10_B/DDR3_DQ26/LPDDR3_DQ22_A20") (pintype "bidirectional+no_connect"))
    )
    (net (code "71") (name "unconnected-(U1E-DDR_DQ11_A{slash}DDR4_DQU5_A{slash}LPDDR4_DQ11_A{slash}DDR3_DQ11{slash}LPDDR3_DQ29-PadT2)") (class "Default")
      (node (ref "U1") (pin "T2") (pinfunction "DDR_DQ11_A/DDR4_DQU5_A/LPDDR4_DQ11_A/DDR3_DQ11/LPDDR3_DQ29_T2") (pintype "bidirectional+no_connect"))
    )
    (net (code "72") (name "unconnected-(U1E-DDR_DQ11_B{slash}DDR4_DQL6_B{slash}LPDDR4_DQ11_B{slash}DDR3_DQ27{slash}LPDDR3_DQ23-PadB20)") (class "Default")
      (node (ref "U1") (pin "B20") (pinfunction "DDR_DQ11_B/DDR4_DQL6_B/LPDDR4_DQ11_B/DDR3_DQ27/LPDDR3_DQ23_B20") (pintype "bidirectional+no_connect"))
    )
    (net (code "73") (name "unconnected-(U1E-DDR_DQ12_A{slash}DDR4_DQU2_A{slash}LPDDR4_DQ12_A{slash}DDR3_DQ12{slash}LPDDR3_DQ26-PadM1)") (class "Default")
      (node (ref "U1") (pin "M1") (pinfunction "DDR_DQ12_A/DDR4_DQU2_A/LPDDR4_DQ12_A/DDR3_DQ12/LPDDR3_DQ26_M1") (pintype "bidirectional+no_connect"))
    )
    (net (code "74") (name "unconnected-(U1E-DDR_DQ12_B{slash}DDR4_DQL7_B{slash}LPDDR4_DQ12_B{slash}DDR3_DQ28{slash}LPDDR3_DQ16-PadA15)") (class "Default")
      (node (ref "U1") (pin "A15") (pinfunction "DDR_DQ12_B/DDR4_DQL7_B/LPDDR4_DQ12_B/DDR3_DQ28/LPDDR3_DQ16_A15") (pintype "bidirectional+no_connect"))
    )
    (net (code "75") (name "unconnected-(U1E-DDR_DQ13_A{slash}DDR4_DQU4_A{slash}LPDDR4_DQ13_A{slash}DDR3_DQ13{slash}LPDDR3_DQ31-Pad1F2)") (class "Default")
      (node (ref "U1") (pin "1F2") (pinfunction "DDR_DQ13_A/DDR4_DQU4_A/LPDDR4_DQ13_A/DDR3_DQ13/LPDDR3_DQ31_1F2") (pintype "bidirectional+no_connect"))
    )
    (net (code "76") (name "unconnected-(U1E-DDR_DQ13_B{slash}DDR4_DQL5_B{slash}LPDDR4_DQ13_B{slash}DDR3_DQ29{slash}LPDDR3_DQ17-PadB15)") (class "Default")
      (node (ref "U1") (pin "B15") (pinfunction "DDR_DQ13_B/DDR4_DQL5_B/LPDDR4_DQ13_B/DDR3_DQ29/LPDDR3_DQ17_B15") (pintype "bidirectional+no_connect"))
    )
    (net (code "77") (name "unconnected-(U1E-DDR_DQ14_A{slash}DDR4_DQU6_A{slash}LPDDR4_DQ14_A{slash}DDR3_DQ14{slash}LPDDR3_DQ30-Pad1F1)") (class "Default")
      (node (ref "U1") (pin "1F1") (pinfunction "DDR_DQ14_A/DDR4_DQU6_A/LPDDR4_DQ14_A/DDR3_DQ14/LPDDR3_DQ30_1F1") (pintype "bidirectional+no_connect"))
    )
    (net (code "78") (name "unconnected-(U1E-DDR_DQ14_B{slash}DDR4_DQL1_B{slash}LPDDR4_DQ14_B{slash}DDR3_DQ30{slash}LPDDR3_DQ20-Pad1C10)") (class "Default")
      (node (ref "U1") (pin "1C10") (pinfunction "DDR_DQ14_B/DDR4_DQL1_B/LPDDR4_DQ14_B/DDR3_DQ30/LPDDR3_DQ20_1C10") (pintype "bidirectional+no_connect"))
    )
    (net (code "79") (name "unconnected-(U1E-DDR_DQ15_A{slash}DDR4_DQU0_A{slash}LPDDR4_DQ15_A{slash}DDR3_DQ15{slash}LPDDR3_DQ27-Pad1G2)") (class "Default")
      (node (ref "U1") (pin "1G2") (pinfunction "DDR_DQ15_A/DDR4_DQU0_A/LPDDR4_DQ15_A/DDR3_DQ15/LPDDR3_DQ27_1G2") (pintype "bidirectional+no_connect"))
    )
    (net (code "80") (name "unconnected-(U1E-DDR_DQ15_B{slash}DDR4_DQL3_B{slash}LPDDR4_DQ15_B{slash}DDR3_DQ31{slash}LPDDR3_DQ21-PadB16)") (class "Default")
      (node (ref "U1") (pin "B16") (pinfunction "DDR_DQ15_B/DDR4_DQL3_B/LPDDR4_DQ15_B/DDR3_DQ31/LPDDR3_DQ21_B16") (pintype "bidirectional+no_connect"))
    )
    (net (code "81") (name "unconnected-(U1E-DDR_DQS0N_A{slash}DDR4_DQSL_N_A{slash}LPDDR4_DQS0N_A{slash}DDR3_DQS0N{slash}LPDDR3_DQS1N-PadH1)") (class "Default")
      (node (ref "U1") (pin "H1") (pinfunction "DDR_DQS0N_A/DDR4_DQSL_N_A/LPDDR4_DQS0N_A/DDR3_DQS0N/LPDDR3_DQS1N_H1") (pintype "bidirectional+no_connect"))
    )
    (net (code "82") (name "unconnected-(U1E-DDR_DQS0N_B{slash}DDR4_DQSU_N_B{slash}LPDDR4_DQS0N_B{slash}DDR3_DQS2N{slash}LPDDR3_DQS0N-PadA12)") (class "Default")
      (node (ref "U1") (pin "A12") (pinfunction "DDR_DQS0N_B/DDR4_DQSU_N_B/LPDDR4_DQS0N_B/DDR3_DQS2N/LPDDR3_DQS0N_A12") (pintype "bidirectional+no_connect"))
    )
    (net (code "83") (name "unconnected-(U1E-DDR_DQS0P_A{slash}DDR4_DQSL_P_A{slash}LPDDR4_DQS0P_A{slash}DDR3_DQS0P{slash}LPDDR3_DQS1P-PadH2)") (class "Default")
      (node (ref "U1") (pin "H2") (pinfunction "DDR_DQS0P_A/DDR4_DQSL_P_A/LPDDR4_DQS0P_A/DDR3_DQS0P/LPDDR3_DQS1P_H2") (pintype "bidirectional+no_connect"))
    )
    (net (code "84") (name "unconnected-(U1E-DDR_DQS0P_B{slash}DDR4_DQSU_P_B{slash}LPDDR4_DQS0P_B{slash}DDR3_DQS2P{slash}LPDDR3_DQS0P-PadA13)") (class "Default")
      (node (ref "U1") (pin "A13") (pinfunction "DDR_DQS0P_B/DDR4_DQSU_P_B/LPDDR4_DQS0P_B/DDR3_DQS2P/LPDDR3_DQS0P_A13") (pintype "bidirectional+no_connect"))
    )
    (net (code "85") (name "unconnected-(U1E-DDR_DQS1N_A{slash}DDR4_DQSU_N_A{slash}LPDDR4_DQS1N_A{slash}DDR3_DQS1N{slash}LPDDR3_DQS3N-PadN2)") (class "Default")
      (node (ref "U1") (pin "N2") (pinfunction "DDR_DQS1N_A/DDR4_DQSU_N_A/LPDDR4_DQS1N_A/DDR3_DQS1N/LPDDR3_DQS3N_N2") (pintype "bidirectional+no_connect"))
    )
    (net (code "86") (name "unconnected-(U1E-DDR_DQS1N_B{slash}DDR4_DQSL_N_B{slash}LPDDR4_DQS1N_B{slash}DDR3_DQS3N{slash}LPDDR3_DQS2N-PadB17)") (class "Default")
      (node (ref "U1") (pin "B17") (pinfunction "DDR_DQS1N_B/DDR4_DQSL_N_B/LPDDR4_DQS1N_B/DDR3_DQS3N/LPDDR3_DQS2N_B17") (pintype "bidirectional+no_connect"))
    )
    (net (code "87") (name "unconnected-(U1E-DDR_DQS1P_A{slash}DDR4_DQSU_P_A{slash}LPDDR4_DQS1P_A{slash}DDR3_DQS1P{slash}LPDDR3_DQS3P-PadN1)") (class "Default")
      (node (ref "U1") (pin "N1") (pinfunction "DDR_DQS1P_A/DDR4_DQSU_P_A/LPDDR4_DQS1P_A/DDR3_DQS1P/LPDDR3_DQS3P_N1") (pintype "bidirectional+no_connect"))
    )
    (net (code "88") (name "unconnected-(U1E-DDR_DQS1P_B{slash}DDR4_DQSL_P_B{slash}LPDDR4_DQS1P_B{slash}DDR3_DQS3P{slash}LPDDR3_DQS2P-PadA17)") (class "Default")
      (node (ref "U1") (pin "A17") (pinfunction "DDR_DQS1P_B/DDR4_DQSL_P_B/LPDDR4_DQS1P_B/DDR3_DQS3P/LPDDR3_DQS2P_A17") (pintype "bidirectional+no_connect"))
    )
    (net (code "89") (name "unconnected-(U1E-DDR_RZQ-Pad1F3)") (class "Default")
      (node (ref "U1") (pin "1F3") (pinfunction "DDR_RZQ_1F3") (pintype "bidirectional+no_connect"))
    )
    (net (code "90") (name "unconnected-(U1E-DDR_VREFOUT-Pad1H3)") (class "Default")
      (node (ref "U1") (pin "1H3") (pinfunction "DDR_VREFOUT_1H3") (pintype "output+no_connect"))
    )
    (net (code "91") (name "unconnected-(U1E-~{ACT}{slash}~{LPDDR}4_~{CKE}1_~{B}{slash}~{DDR}3_~{CAS}{slash}-{slash}~{AC}1~{7}-Pad1A2)") (class "Default")
      (node (ref "U1") (pin "1A2") (pinfunction "~{ACT}/~{LPDDR}4_~{CKE}1_~{B}/~{DDR}3_~{CAS}/-/~{AC}1~{7}_1A2") (pintype "bidirectional+no_connect"))
    )
    (net (code "92") (name "unconnected-(U1E-~{CS0}-Pad1B5)") (class "Default")
      (node (ref "U1") (pin "1B5") (pinfunction "~{CS0}_1B5") (pintype "bidirectional+no_connect"))
    )
    (net (code "93") (name "unconnected-(U1E-~{CS0}-PadB3)") (class "Default")
      (node (ref "U1") (pin "B3") (pinfunction "~{CS0}_B3") (pintype "bidirectional+no_connect"))
    )
    (net (code "94") (name "unconnected-(U1E-~{CS1}-Pad1A5)") (class "Default")
      (node (ref "U1") (pin "1A5") (pinfunction "~{CS1}_1A5") (pintype "bidirectional+no_connect"))
    )
    (net (code "95") (name "unconnected-(U1E-~{CS1}-PadA3)") (class "Default")
      (node (ref "U1") (pin "A3") (pinfunction "~{CS1}_A3") (pintype "bidirectional+no_connect"))
    )
    (net (code "96") (name "unconnected-(U1E-~{RESET}-Pad1C7)") (class "Default")
      (node (ref "U1") (pin "1C7") (pinfunction "~{RESET}_1C7") (pintype "bidirectional+no_connect"))
    )
    (net (code "97") (name "unconnected-(U2A-VPP1-PadB1)") (class "Default")
      (node (ref "U2") (pin "B1") (pinfunction "VPP1_B1") (pintype "power_in"))
    )
    (net (code "98") (name "unconnected-(U2A-VPP2-PadR9)") (class "Default")
      (node (ref "U2") (pin "R9") (pinfunction "VPP2_R9") (pintype "power_in"))
    )
    (net (code "99") (name "unconnected-(U2A-VREFCA-PadM1)") (class "Default")
      (node (ref "U2") (pin "M1") (pinfunction "VREFCA_M1") (pintype "power_in"))
    )
    (net (code "100") (name "unconnected-(U2B-ACT_N-PadL3)") (class "Default")
      (node (ref "U2") (pin "L3") (pinfunction "ACT_N_L3") (pintype "input"))
    )
    (net (code "101") (name "unconnected-(U2B-ALERT_N-PadP9)") (class "Default")
      (node (ref "U2") (pin "P9") (pinfunction "ALERT_N_P9") (pintype "output"))
    )
    (net (code "102") (name "unconnected-(U2B-BA0-PadN2)") (class "Default")
      (node (ref "U2") (pin "N2") (pinfunction "BA0_N2") (pintype "input"))
    )
    (net (code "103") (name "unconnected-(U2B-BA1-PadN8)") (class "Default")
      (node (ref "U2") (pin "N8") (pinfunction "BA1_N8") (pintype "input"))
    )
    (net (code "104") (name "unconnected-(U2B-BG0-PadM2)") (class "Default")
      (node (ref "U2") (pin "M2") (pinfunction "BG0_M2") (pintype "input"))
    )
    (net (code "105") (name "unconnected-(U2B-CKE-PadK2)") (class "Default")
      (node (ref "U2") (pin "K2") (pinfunction "CKE_K2") (pintype "input"))
    )
    (net (code "106") (name "unconnected-(U2B-CS_N-PadL7)") (class "Default")
      (node (ref "U2") (pin "L7") (pinfunction "CS_N_L7") (pintype "input"))
    )
    (net (code "107") (name "unconnected-(U2B-NC-PadT7)") (class "Default")
      (node (ref "U2") (pin "T7") (pinfunction "NC_T7") (pintype "passive+no_connect"))
    )
    (net (code "108") (name "unconnected-(U2B-NF{slash}LDM_N{slash}LDBI_N-PadE7)") (class "Default")
      (node (ref "U2") (pin "E7") (pinfunction "NF/LDM_N/LDBI_N_E7") (pintype "bidirectional"))
    )
    (net (code "109") (name "unconnected-(U2B-NF{slash}UDM_N{slash}UDBI_N-PadE2)") (class "Default")
      (node (ref "U2") (pin "E2") (pinfunction "NF/UDM_N/UDBI_N_E2") (pintype "bidirectional"))
    )
    (net (code "110") (name "unconnected-(U2B-ODT-PadK3)") (class "Default")
      (node (ref "U2") (pin "K3") (pinfunction "ODT_K3") (pintype "input"))
    )
    (net (code "111") (name "unconnected-(U2B-PAR-PadT3)") (class "Default")
      (node (ref "U2") (pin "T3") (pinfunction "PAR_T3") (pintype "input"))
    )
    (net (code "112") (name "unconnected-(U2B-TEN-PadN9)") (class "Default")
      (node (ref "U2") (pin "N9") (pinfunction "TEN_N9") (pintype "input"))
    )
    (net (code "113") (name "unconnected-(U2B-ZQ-PadF9)") (class "Default")
      (node (ref "U2") (pin "F9") (pinfunction "ZQ_F9") (pintype "passive"))
    )
    (net (code "114") (name "unconnected-(U2B-~{RESET_N}-PadP1)") (class "Default")
      (node (ref "U2") (pin "P1") (pinfunction "~{RESET_N}_P1") (pintype "input"))
    )
    (net (code "115") (name "unconnected-(U2C-LDQS_C-PadF3)") (class "Default")
      (node (ref "U2") (pin "F3") (pinfunction "LDQS_C_F3") (pintype "bidirectional"))
    )
    (net (code "116") (name "unconnected-(U2C-LDQS_T-PadG3)") (class "Default")
      (node (ref "U2") (pin "G3") (pinfunction "LDQS_T_G3") (pintype "bidirectional"))
    )
    (net (code "117") (name "unconnected-(U2C-UDQS_C-PadA7)") (class "Default")
      (node (ref "U2") (pin "A7") (pinfunction "UDQS_C_A7") (pintype "bidirectional"))
    )
    (net (code "118") (name "unconnected-(U2C-UDQS_T-PadB7)") (class "Default")
      (node (ref "U2") (pin "B7") (pinfunction "UDQS_T_B7") (pintype "bidirectional"))
    )
  )
)
